# Morpheus_LDO.net
KiCad netlist of a schematic drawn in Altium Designer
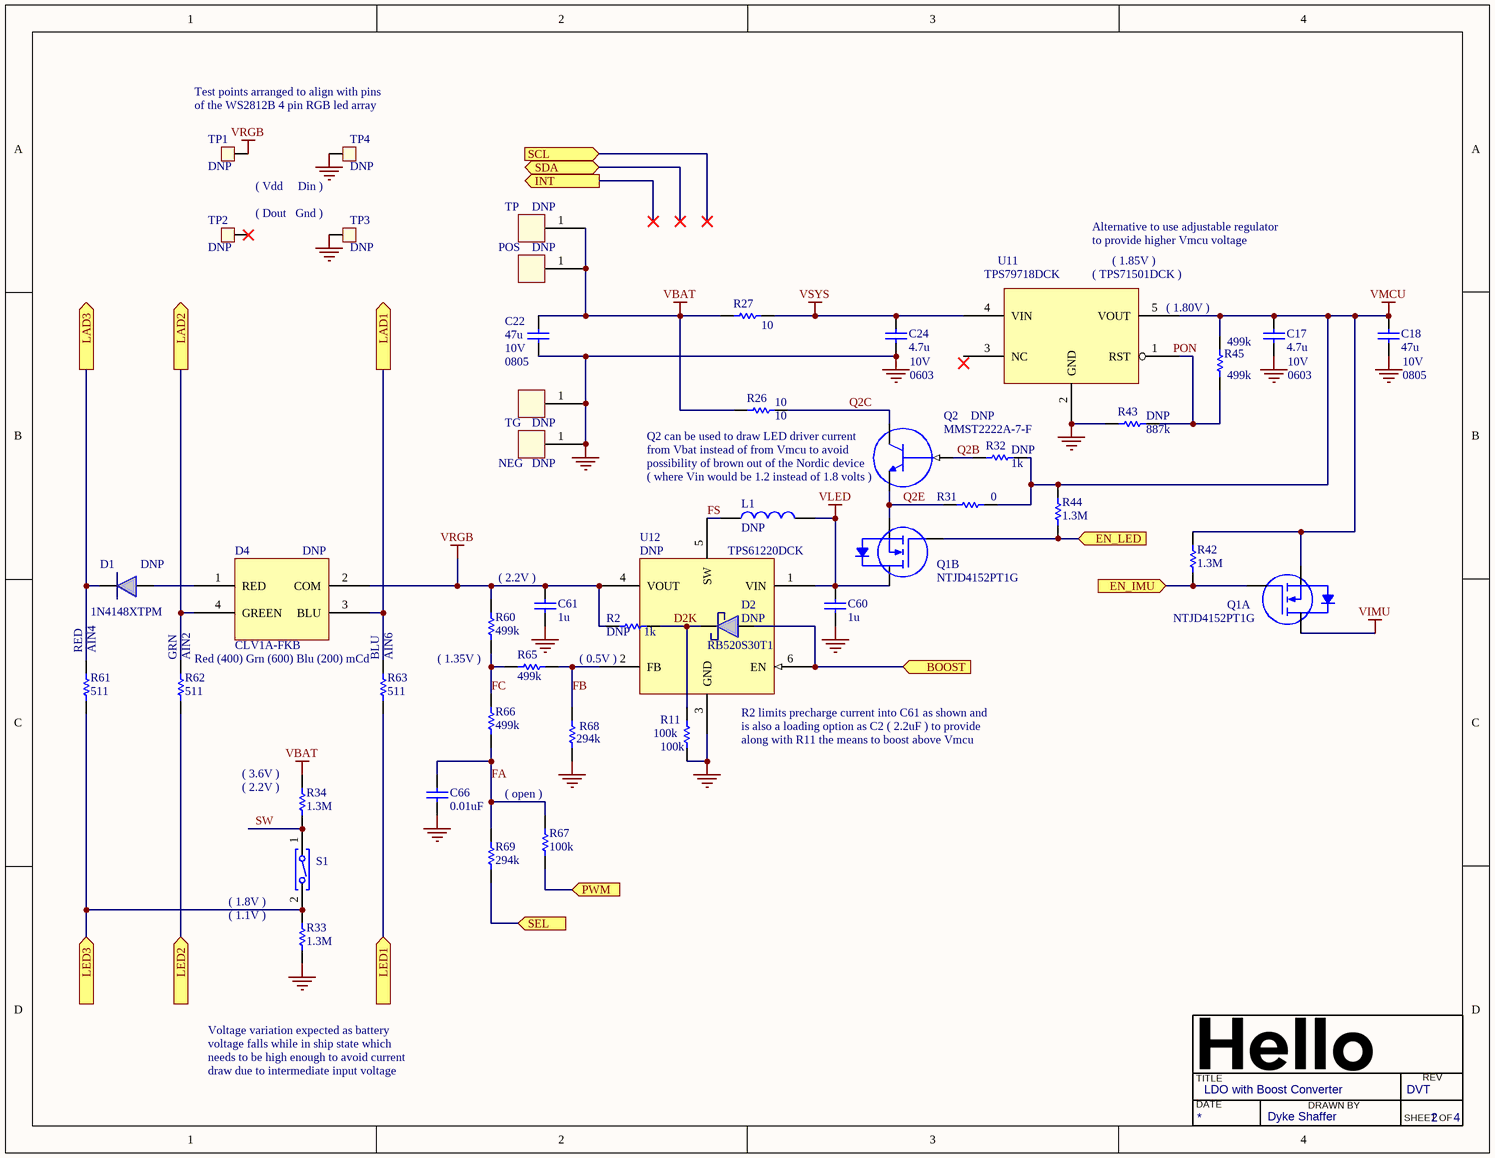
[diagram p0: Morpheus_LDO.SchDoc]

(export (version "E")
  (design (tool "Eeschema 10.0.6"))
  (components
    (comp (ref "C17")
      (value "4.7u")
      (footprint "CAP0603_SENSE_DVT")
      (description "CAP CER 4.7UF 10V 20% X5R 0603")
      (fields (field (name "SIZE") "0603") (field (name "TOLERANCE") "20%") (field (name "VOLTAGE") "10V"))
      (libsource (lib "Morpheus_pill") (part "C_4.7u_20_10_X5R_0603"))
    )
    (comp (ref "C18")
      (value "47u")
      (footprint "CAP0805_SENSE_DVT")
      (description "CAP CER 47UF 10V 20% X5R 0805")
      (fields (field (name "SIZE") "0805") (field (name "TOLERANCE") "20%") (field (name "VOLTAGE") "10V"))
      (libsource (lib "Morpheus_pill") (part "C_47u_20_10_X5R_0805"))
    )
    (comp (ref "C22")
      (value "47u")
      (footprint "CAP0805_SENSE_DVT")
      (description "CAP CER 47UF 10V 20% X5R 0805")
      (fields (field (name "SIZE") "0805") (field (name "TOLERANCE") "20%") (field (name "VOLTAGE") "10V"))
      (libsource (lib "Morpheus_pill") (part "C_47u_20_10_X5R_0805"))
    )
    (comp (ref "C24")
      (value "4.7u")
      (footprint "CAP0603_SENSE_DVT")
      (description "CAP CER 4.7UF 10V 20% X5R 0603")
      (fields (field (name "SIZE") "0603") (field (name "TOLERANCE") "20%") (field (name "VOLTAGE") "10V"))
      (libsource (lib "Morpheus_pill") (part "C_4.7u_20_10_X5R_0603"))
    )
    (comp (ref "C60")
      (value "1u")
      (footprint "CAP0402_SENSE_DVT")
      (description "CAP CER 1UF 6.3V 10% X5R 0402")
      (fields (field (name "TOLERANCE") "10%") (field (name "VOLTAGE") "6.3V"))
      (libsource (lib "Morpheus_pill") (part "C_1u_10_6.3_X5R_0402"))
    )
    (comp (ref "C61")
      (value "1u")
      (footprint "CAP0402_SENSE_DVT")
      (description "CAP CER 1UF 6.3V 10% X5R 0402")
      (fields (field (name "TOLERANCE") "10%") (field (name "VOLTAGE") "6.3V"))
      (libsource (lib "Morpheus_pill") (part "C_1u_10_6.3_X5R_0402"))
    )
    (comp (ref "C66")
      (value "0.01uF")
      (footprint "CAP0402_SENSE_DVT")
      (description "CAP CER 10000PF 50V 10% X7R 0402")
      (fields (field (name "TOLERANCE") "10%") (field (name "VOLTAGE") "50"))
      (libsource (lib "Morpheus_pill") (part "C_10000p_10_50_X7R_0402"))
    )
    (comp (ref "D1")
      (value "DNP")
      (footprint "SOD523")
      (description "Silicon diode, 30V 200mA")
      (fields (field (name "PN") "1N4148XTPM"))
      (libsource (lib "Morpheus_pill") (part "1N4148XTPM"))
    )
    (comp (ref "D2")
      (value "DNP")
      (footprint "SOD523")
      (description "Schottky diode, 30V 200mA")
      (fields (field (name "PN") "RB520S30T1"))
      (libsource (lib "Morpheus_pill") (part "RB520S30T1"))
    )
    (comp (ref "D4")
      (value "DNP")
      (footprint "PLCC150X290P280X320X190-4")
      (description "RGB LED Array")
      (fields
        (field (name "PN") "CLV1A-FKB")
        (field (name "ALTIUM_VALUE") "Red (400) Grn (600) Blu (200) mCd")
      )
      (libsource (lib "Morpheus_pill") (part "CLV1A-FKB"))
    )
    (comp (ref "L1")
      (value "DNP")
      (footprint "IND_1206")
      (description "SMD power inductor, 2.2uH")
      (fields (field (name "TOLERANCE") "20%"))
      (libsource (lib "Morpheus_pill") (part "L_2.2u_1206"))
    )
    (comp (ref "NEG")
      (value "DNP")
      (footprint "TP0875x050")
      (description "Single-pad test point")
      (libsource (lib "Morpheus_pill") (part "5016"))
    )
    (comp (ref "POS")
      (value "DNP")
      (footprint "TP0875x050")
      (description "Single-pad test point")
      (libsource (lib "Morpheus_pill") (part "5016"))
    )
    (comp (ref "Q1")
      (value "NTJD4152PT1G")
      (footprint "SOT65P212X110-6N")
      (description "MOSFET 2P-CH 20V 880MA SOT-363")
      (libsource (lib "") (part "NTJD4152PT1G_1"))
    )
    (comp (ref "Q2")
      (value "DNP")
      (footprint "SOT-323")
      (description "NPN Transistor, 20V, 600mA")
      (fields (field (name "PN") "MMST2222A-7-F"))
      (libsource (lib "Morpheus_pill") (part "MMST2222A"))
    )
    (comp (ref "R2")
      (value "DNP")
      (footprint "RES0402_SENSE_DVT")
      (description "Chip Resistor")
      (fields
        (field (name "ALTIUM_VALUE") "1k")
        (field (name "TOLERANCE") "1 %")
        (field (name "POWER") "0.1 W")
      )
      (libsource (lib "Morpheus_pill") (part "R_1k_1_0.1_0402"))
    )
    (comp (ref "R11")
      (value "100k")
      (footprint "RES0402_SENSE_DVT")
      (description "RES SMD 100K OHM 1% 1/16W 0402")
      (fields
        (field (name "ALTIUM_VALUE") "100k")
        (field (name "TOLERANCE") "1 %")
        (field (name "POWER") "0.1 W")
      )
      (libsource (lib "Morpheus_pill") (part "R_100k_1_0.1_0402"))
    )
    (comp (ref "R26")
      (value "10")
      (footprint "RES0402_SENSE_DVT")
      (description "RES SMD 10 OHM 1% 1/16W 0402")
      (fields
        (field (name "ALTIUM_VALUE") "10")
        (field (name "TOLERANCE") "1 %")
        (field (name "POWER") "0.1 W")
      )
      (libsource (lib "Morpheus_pill") (part "R_10_1_0.1_0402"))
    )
    (comp (ref "R27")
      (value "10")
      (footprint "RES0402_SENSE_DVT")
      (description "RES SMD 10 OHM 1% 1/16W 0402")
      (fields (field (name "TOLERANCE") "1 %") (field (name "POWER") "0.1 W"))
      (libsource (lib "Morpheus_pill") (part "R_10_1_0.1_0402"))
    )
    (comp (ref "R31")
      (value "0")
      (footprint "RES0402-SENSE-DVT")
      (description "RES SMD 0.0 OHM JUMPER 1/16W")
      (fields (field (name "TOLERANCE") "Jumper") (field (name "POWER") "0.1 W"))
      (libsource (lib "Morpheus_pill") (part "R_0_jumper_0.1_0402"))
    )
    (comp (ref "R32")
      (value "DNP")
      (footprint "RES0402_SENSE_DVT")
      (description "Chip Resistor")
      (fields
        (field (name "ALTIUM_VALUE") "1k")
        (field (name "TOLERANCE") "1 %")
        (field (name "POWER") "0.1 W")
      )
      (libsource (lib "Morpheus_pill") (part "R_1k_1_0.1_0402"))
    )
    (comp (ref "R33")
      (value "1.3M")
      (footprint "RES0402_SENSE_DVT")
      (description "RES 1.3M OHM 1/10W 5% 0402 SMD")
      (fields (field (name "TOLERANCE") "5 %") (field (name "POWER") "0.1 W"))
      (libsource (lib "Morpheus_pill") (part "R_1.3M_5_0.1_0402"))
    )
    (comp (ref "R34")
      (value "1.3M")
      (footprint "RES0402_SENSE_DVT")
      (description "RES 1.3M OHM 1/10W 5% 0402 SMD")
      (fields (field (name "TOLERANCE") "5 %") (field (name "POWER") "0.1 W"))
      (libsource (lib "Morpheus_pill") (part "R_1.3M_5_0.1_0402"))
    )
    (comp (ref "R42")
      (value "1.3M")
      (footprint "RES0402_SENSE_DVT")
      (description "RES 1.3M OHM 1/10W 5% 0402 SMD")
      (fields (field (name "TOLERANCE") "5 %") (field (name "POWER") "0.1 W"))
      (libsource (lib "Morpheus_pill") (part "R_1.3M_5_0.1_0402"))
    )
    (comp (ref "R43")
      (value "DNP")
      (footprint "RES0402_SENSE_DVT")
      (description "Chip Resistor")
      (fields
        (field (name "ALTIUM_VALUE") "887k")
        (field (name "TOLERANCE") "1 %")
        (field (name "POWER") "0.1 W")
      )
      (libsource (lib "Morpheus_pill") (part "R_887k_1_0.1_0402"))
    )
    (comp (ref "R44")
      (value "1.3M")
      (footprint "RES0402_SENSE_DVT")
      (description "RES 1.3M OHM 1/10W 5% 0402 SMD")
      (fields (field (name "TOLERANCE") "5 %") (field (name "POWER") "0.1 W"))
      (libsource (lib "Morpheus_pill") (part "R_1.3M_5_0.1_0402"))
    )
    (comp (ref "R45")
      (value "499k")
      (footprint "RES0402_SENSE_DVT")
      (description "RES 499K OHM 1/10W 1% 0402 SMD")
      (fields
        (field (name "ALTIUM_VALUE") "499k")
        (field (name "TOLERANCE") "1 %")
        (field (name "POWER") "0.1 W")
      )
      (libsource (lib "Morpheus_pill") (part "R_499k_1_0.1_0402"))
    )
    (comp (ref "R60")
      (value "499k")
      (footprint "RES0402_SENSE_DVT")
      (description "RES 499K OHM 1/10W 1% 0402 SMD")
      (fields (field (name "TOLERANCE") "1 %") (field (name "POWER") "0.1 W"))
      (libsource (lib "Morpheus_pill") (part "R_499k_1_0.1_0402"))
    )
    (comp (ref "R61")
      (value "511")
      (footprint "RES0402_SENSE_DVT")
      (description "RES 511 OHM 1/10W 1% 0402 SMD")
      (fields (field (name "TOLERANCE") "1 %") (field (name "POWER") "0.1 W"))
      (libsource (lib "Morpheus_pill") (part "R_511_1_0.1_0402"))
    )
    (comp (ref "R62")
      (value "511")
      (footprint "RES0402_SENSE_DVT")
      (description "RES 511 OHM 1/10W 1% 0402 SMD")
      (fields (field (name "TOLERANCE") "1 %") (field (name "POWER") "0.1 W"))
      (libsource (lib "Morpheus_pill") (part "R_511_1_0.1_0402"))
    )
    (comp (ref "R63")
      (value "511")
      (footprint "RES0402_SENSE_DVT")
      (description "RES 511 OHM 1/10W 1% 0402 SMD")
      (fields (field (name "TOLERANCE") "1 %") (field (name "POWER") "0.1 W"))
      (libsource (lib "Morpheus_pill") (part "R_511_1_0.1_0402"))
    )
    (comp (ref "R65")
      (value "499k")
      (footprint "RES0402_SENSE_DVT")
      (description "RES 499K OHM 1/10W 1% 0402 SMD")
      (fields (field (name "TOLERANCE") "1 %") (field (name "POWER") "0.1 W"))
      (libsource (lib "Morpheus_pill") (part "R_499k_1_0.1_0402"))
    )
    (comp (ref "R66")
      (value "499k")
      (footprint "RES0402_SENSE_DVT")
      (description "RES 499K OHM 1/10W 1% 0402 SMD")
      (fields (field (name "TOLERANCE") "1 %") (field (name "POWER") "0.1 W"))
      (libsource (lib "Morpheus_pill") (part "R_499k_1_0.1_0402"))
    )
    (comp (ref "R67")
      (value "100k")
      (footprint "RES0402_SENSE_DVT")
      (description "RES SMD 100K OHM 1% 1/16W 0402")
      (fields (field (name "TOLERANCE") "1 %") (field (name "POWER") "0.1 W"))
      (libsource (lib "Morpheus_pill") (part "R_100k_1_0.1_0402"))
    )
    (comp (ref "R68")
      (value "294k")
      (footprint "RES0402_SENSE_DVT")
      (description "RES 294K OHM 1/10W 1% 0402 SMD")
      (fields (field (name "TOLERANCE") "1 %") (field (name "POWER") "0.1 W"))
      (libsource (lib "Morpheus_pill") (part "R_294k_1_0.1_0402"))
    )
    (comp (ref "R69")
      (value "294k")
      (footprint "RES0402_SENSE_DVT")
      (description "RES 294K OHM 1/10W 1% 0402 SMD")
      (fields (field (name "TOLERANCE") "1 %") (field (name "POWER") "0.1 W"))
      (libsource (lib "Morpheus_pill") (part "R_294k_1_0.1_0402"))
    )
    (comp (ref "S1")
      (value "REED_SPST_NO")
      (footprint "REED-10x1.8")
      (description "SWITCH REED SPST NO")
      (libsource (lib "Morpheus_pill") (part "SW_REED_SPST_NO"))
    )
    (comp (ref "TG")
      (value "DNP")
      (footprint "TP0875x050")
      (description "Single-pad test point")
      (libsource (lib "Morpheus_pill") (part "5016"))
    )
    (comp (ref "TP")
      (value "DNP")
      (footprint "TP0875x050")
      (description "Single-pad test point")
      (libsource (lib "Morpheus_pill") (part "5016"))
    )
    (comp (ref "TP1")
      (value "DNP")
      (footprint "TP-0.8")
      (description "testpoint")
      (libsource (lib "Morpheus_pill") (part "TP-0.8"))
    )
    (comp (ref "TP2")
      (value "DNP")
      (footprint "TP-0.8")
      (description "testpoint")
      (libsource (lib "Morpheus_pill") (part "TP-0.8"))
    )
    (comp (ref "TP3")
      (value "DNP")
      (footprint "TP-0.8")
      (description "testpoint")
      (libsource (lib "") (part "TP-0.8_1"))
    )
    (comp (ref "TP4")
      (value "DNP")
      (footprint "TP-0.8")
      (description "testpoint")
      (libsource (lib "") (part "TP-0.8_1"))
    )
    (comp (ref "U11")
      (value "TPS79718DCK")
      (footprint "SOT65P212X110-5N")
      (description "LDO Voltage Regulators EP Ultra Lo-Pwr 10Ma LDO Linear Reg")
      (libsource (lib "Morpheus_pill") (part "TPS79718DCK"))
    )
    (comp (ref "U12")
      (value "DNP")
      (footprint "SOT65P212X110-6N")
      (description "Boost Converter")
      (fields (field (name "PN") "TPS61220DCK"))
      (libsource (lib "Morpheus_pill") (part "TPS61220"))
    )
  )
  (nets
    (net (code "1") (name "/BOOST") (class "Default")
      (node (ref "D2") (pin "2") (pinfunction "Anode_2") (pintype "passive"))
      (node (ref "U12") (pin "6") (pinfunction "EN_6") (pintype "input"))
    )
    (net (code "2") (name "/D2K") (class "Default")
      (node (ref "D2") (pin "1") (pinfunction "Cathode_1") (pintype "passive"))
      (node (ref "R11") (pin "2") (pinfunction "2_2") (pintype "passive"))
      (node (ref "R2") (pin "2") (pinfunction "2_2") (pintype "passive"))
    )
    (net (code "3") (name "/EN_IMU") (class "Default")
      (node (ref "Q1") (pin "2") (pinfunction "G1_2") (pintype "passive"))
      (node (ref "R42") (pin "1") (pinfunction "1_1") (pintype "passive"))
    )
    (net (code "4") (name "/EN_LED") (class "Default")
      (node (ref "Q1") (pin "5") (pinfunction "G2_5") (pintype "passive"))
      (node (ref "R44") (pin "1") (pinfunction "1_1") (pintype "passive"))
    )
    (net (code "5") (name "/FA") (class "Default")
      (node (ref "C66") (pin "2") (pinfunction "2_2") (pintype "passive"))
      (node (ref "R66") (pin "1") (pinfunction "1_1") (pintype "passive"))
      (node (ref "R67") (pin "2") (pinfunction "2_2") (pintype "passive"))
      (node (ref "R69") (pin "2") (pinfunction "2_2") (pintype "passive"))
    )
    (net (code "6") (name "/FB") (class "Default")
      (node (ref "R65") (pin "1") (pinfunction "1_1") (pintype "passive"))
      (node (ref "R68") (pin "2") (pinfunction "2_2") (pintype "passive"))
      (node (ref "U12") (pin "2") (pinfunction "FB_2") (pintype "passive"))
    )
    (net (code "7") (name "/FC") (class "Default")
      (node (ref "R60") (pin "1") (pinfunction "1_1") (pintype "passive"))
      (node (ref "R65") (pin "2") (pinfunction "2_2") (pintype "passive"))
      (node (ref "R66") (pin "2") (pinfunction "2_2") (pintype "passive"))
    )
    (net (code "8") (name "/FS") (class "Default")
      (node (ref "L1") (pin "2") (pintype "passive"))
      (node (ref "U12") (pin "5") (pinfunction "SW_5") (pintype "passive"))
    )
    (net (code "10") (name "/LAD1") (class "Default")
      (node (ref "D4") (pin "3") (pinfunction "BLU_3") (pintype "passive"))
      (node (ref "R63") (pin "2") (pinfunction "2_2") (pintype "passive"))
    )
    (net (code "11") (name "/LAD2") (class "Default")
      (node (ref "D4") (pin "4") (pinfunction "GREEN_4") (pintype "passive"))
      (node (ref "R62") (pin "2") (pinfunction "2_2") (pintype "passive"))
    )
    (net (code "12") (name "/LAD3") (class "Default")
      (node (ref "D1") (pin "1") (pinfunction "Cathode_1") (pintype "passive"))
      (node (ref "R61") (pin "2") (pinfunction "2_2") (pintype "passive"))
    )
    (net (code "13") (name "/LED1") (class "Default")
      (node (ref "R63") (pin "1") (pinfunction "1_1") (pintype "passive"))
    )
    (net (code "14") (name "/LED2") (class "Default")
      (node (ref "R62") (pin "1") (pinfunction "1_1") (pintype "passive"))
    )
    (net (code "15") (name "/LED3") (class "Default")
      (node (ref "R33") (pin "2") (pinfunction "2_2") (pintype "passive"))
      (node (ref "R61") (pin "1") (pinfunction "1_1") (pintype "passive"))
      (node (ref "S1") (pin "2") (pinfunction "2_2") (pintype "passive"))
    )
    (net (code "17") (name "/PWM") (class "Default")
      (node (ref "R67") (pin "1") (pinfunction "1_1") (pintype "passive"))
    )
    (net (code "18") (name "/Q2B") (class "Default")
      (node (ref "Q2") (pin "1") (pinfunction "IN_1") (pintype "input"))
      (node (ref "R32") (pin "1") (pinfunction "1_1") (pintype "passive"))
    )
    (net (code "19") (name "/Q2C") (class "Default")
      (node (ref "Q2") (pin "3") (pinfunction "OUT_3") (pintype "open_collector"))
      (node (ref "R26") (pin "2") (pinfunction "2_2") (pintype "passive"))
    )
    (net (code "20") (name "/Q2E") (class "Default")
      (node (ref "Q1") (pin "4") (pinfunction "S2_4") (pintype "passive"))
      (node (ref "Q2") (pin "2") (pinfunction "GND_2") (pintype "power_in"))
      (node (ref "R31") (pin "1") (pinfunction "1_1") (pintype "passive"))
    )
    (net (code "23") (name "/SEL") (class "Default")
      (node (ref "R69") (pin "1") (pinfunction "1_1") (pintype "passive"))
    )
    (net (code "24") (name "/SW") (class "Default")
      (node (ref "R34") (pin "1") (pinfunction "1_1") (pintype "passive"))
      (node (ref "S1") (pin "1") (pinfunction "1_1") (pintype "passive"))
    )
    (net (code "25") (name "GND") (class "Default")
      (node (ref "C17") (pin "1") (pinfunction "1_1") (pintype "passive"))
      (node (ref "C18") (pin "1") (pinfunction "1_1") (pintype "passive"))
      (node (ref "C22") (pin "1") (pinfunction "1_1") (pintype "passive"))
      (node (ref "C24") (pin "1") (pinfunction "1_1") (pintype "passive"))
      (node (ref "C60") (pin "1") (pinfunction "1_1") (pintype "passive"))
      (node (ref "C61") (pin "1") (pinfunction "1_1") (pintype "passive"))
      (node (ref "C66") (pin "1") (pinfunction "1_1") (pintype "passive"))
      (node (ref "NEG") (pin "1") (pinfunction "1_1") (pintype "passive"))
      (node (ref "R11") (pin "1") (pinfunction "1_1") (pintype "passive"))
      (node (ref "R33") (pin "1") (pinfunction "1_1") (pintype "passive"))
      (node (ref "R43") (pin "1") (pinfunction "1_1") (pintype "passive"))
      (node (ref "R68") (pin "1") (pinfunction "1_1") (pintype "passive"))
      (node (ref "TG") (pin "1") (pinfunction "1_1") (pintype "passive"))
      (node (ref "TP3") (pin "1") (pinfunction "1_1") (pintype "passive"))
      (node (ref "TP4") (pin "1") (pinfunction "1_1") (pintype "passive"))
      (node (ref "U11") (pin "2") (pinfunction "GND_2") (pintype "power_in"))
      (node (ref "U12") (pin "3") (pinfunction "GND_3") (pintype "power_in"))
    )
    (net (code "26") (name "Net-(D1-Anode)") (class "Default")
      (node (ref "D1") (pin "2") (pinfunction "Anode_2") (pintype "passive"))
      (node (ref "D4") (pin "1") (pinfunction "RED_1") (pintype "passive"))
    )
    (net (code "27") (name "Net-(U11-RST)") (class "Default")
      (node (ref "R43") (pin "2") (pinfunction "2_2") (pintype "passive"))
      (node (ref "R45") (pin "1") (pinfunction "1_1") (pintype "passive"))
      (node (ref "U11") (pin "1") (pinfunction "RST_1") (pintype "open_collector"))
    )
    (net (code "28") (name "VBAT") (class "Default")
      (node (ref "C22") (pin "2") (pinfunction "2_2") (pintype "passive"))
      (node (ref "POS") (pin "1") (pinfunction "1_1") (pintype "passive"))
      (node (ref "R26") (pin "1") (pinfunction "1_1") (pintype "passive"))
      (node (ref "R27") (pin "1") (pinfunction "1_1") (pintype "passive"))
      (node (ref "R34") (pin "2") (pinfunction "2_2") (pintype "passive"))
      (node (ref "TP") (pin "1") (pinfunction "1_1") (pintype "passive"))
    )
    (net (code "29") (name "VIMU") (class "Default")
      (node (ref "Q1") (pin "6") (pinfunction "D1_6") (pintype "passive"))
    )
    (net (code "30") (name "VLED") (class "Default")
      (node (ref "C60") (pin "2") (pinfunction "2_2") (pintype "passive"))
      (node (ref "L1") (pin "1") (pintype "passive"))
      (node (ref "Q1") (pin "3") (pinfunction "D2_3") (pintype "passive"))
      (node (ref "U12") (pin "1") (pinfunction "VIN_1") (pintype "power_in"))
    )
    (net (code "31") (name "VMCU") (class "Default")
      (node (ref "C17") (pin "2") (pinfunction "2_2") (pintype "passive"))
      (node (ref "C18") (pin "2") (pinfunction "2_2") (pintype "passive"))
      (node (ref "Q1") (pin "1") (pinfunction "S1_1") (pintype "passive"))
      (node (ref "R31") (pin "2") (pinfunction "2_2") (pintype "passive"))
      (node (ref "R32") (pin "2") (pinfunction "2_2") (pintype "passive"))
      (node (ref "R42") (pin "2") (pinfunction "2_2") (pintype "passive"))
      (node (ref "R44") (pin "2") (pinfunction "2_2") (pintype "passive"))
      (node (ref "R45") (pin "2") (pinfunction "2_2") (pintype "passive"))
      (node (ref "U11") (pin "5") (pinfunction "VOUT_5") (pintype "power_in"))
    )
    (net (code "32") (name "VRGB") (class "Default")
      (node (ref "C61") (pin "2") (pinfunction "2_2") (pintype "passive"))
      (node (ref "D4") (pin "2") (pinfunction "COM_2") (pintype "passive"))
      (node (ref "R2") (pin "1") (pinfunction "1_1") (pintype "passive"))
      (node (ref "R60") (pin "2") (pinfunction "2_2") (pintype "passive"))
      (node (ref "TP1") (pin "1") (pinfunction "1_1") (pintype "passive"))
      (node (ref "U12") (pin "4") (pinfunction "VOUT_4") (pintype "power_in"))
    )
    (net (code "33") (name "VSYS") (class "Default")
      (node (ref "C24") (pin "2") (pinfunction "2_2") (pintype "passive"))
      (node (ref "R27") (pin "2") (pinfunction "2_2") (pintype "passive"))
      (node (ref "U11") (pin "4") (pinfunction "VIN_4") (pintype "power_in"))
    )
    (net (code "34") (name "unconnected-(TP2-Pad1)") (class "Default")
      (node (ref "TP2") (pin "1") (pinfunction "1_1") (pintype "passive+no_connect"))
    )
    (net (code "35") (name "unconnected-(U11-NC-Pad3)") (class "Default")
      (node (ref "U11") (pin "3") (pinfunction "NC_3") (pintype "passive"))
    )
  )
)
